# drone_controller.net
KiCad netlist of a schematic drawn in EAGLE
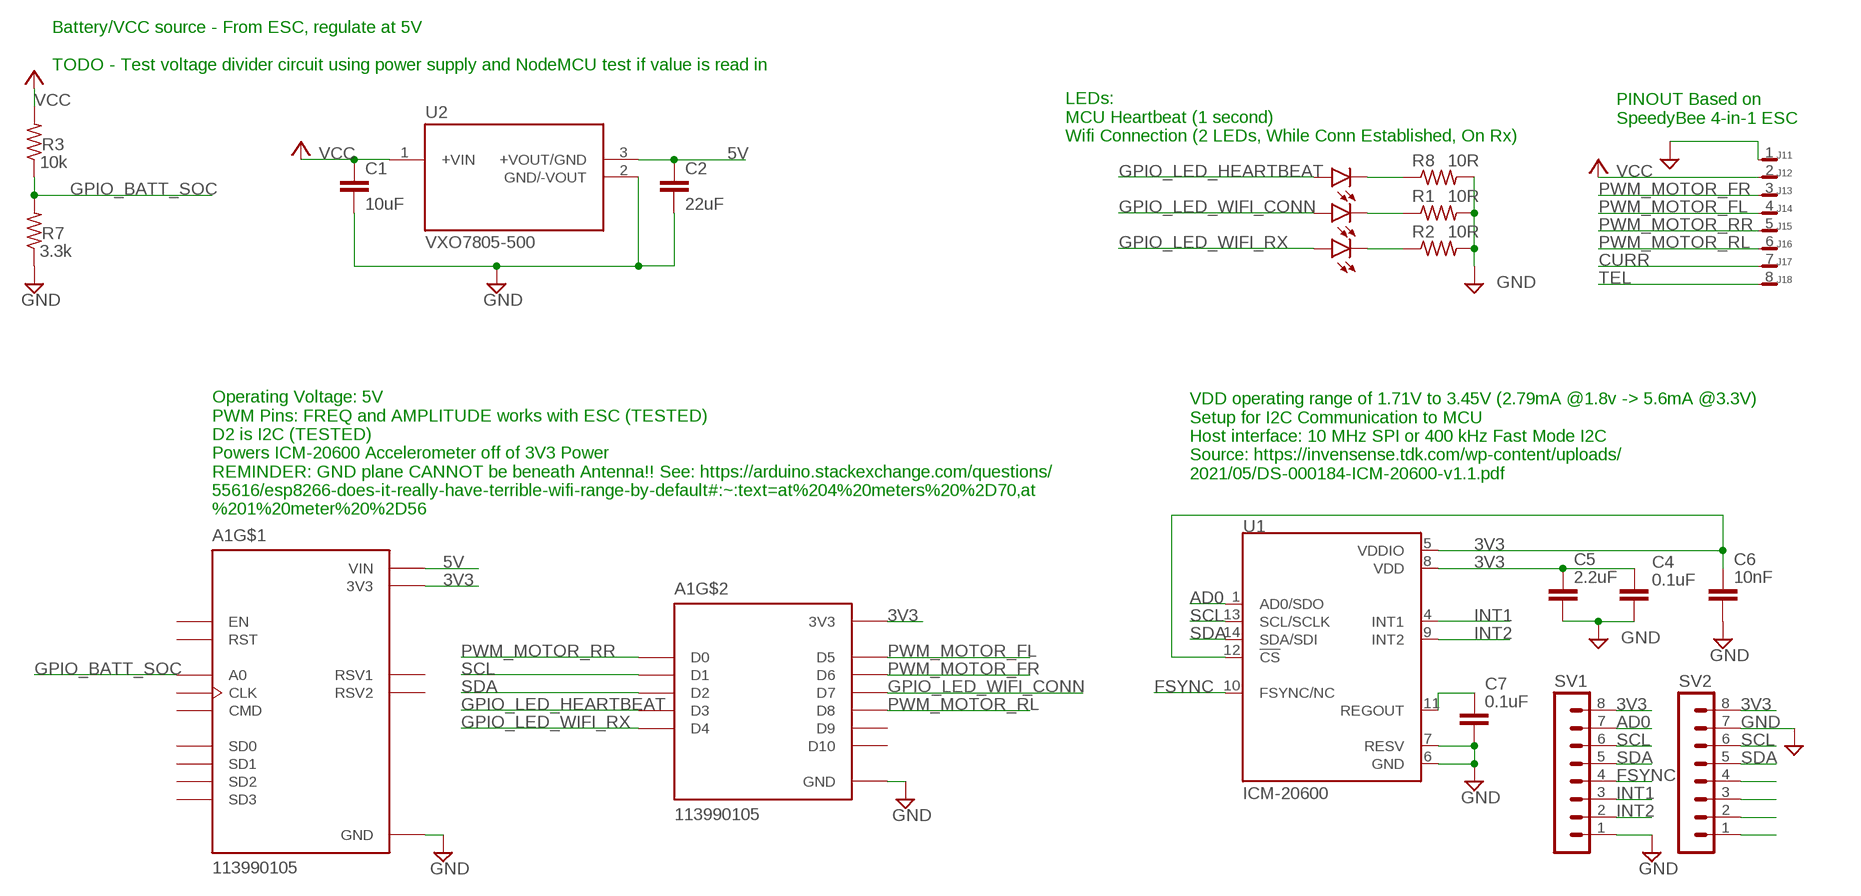
[diagram p0: schematic, sheet 1]

(export (version "E")
  (design (tool "Eeschema 10.0.6"))
  (components
    (comp (ref "A1")
      (value "113990105")
      (footprint "eagle-import:SEEED_113990105")
      (fields (field (name "MF") "Seeed Technology") (field (name "MP") "NodeMCU v2"))
      (libsource (lib "eagle-import") (part "113990105"))
    )
    (comp (ref "C1")
      (value "10uF")
      (footprint "eagle-import:C2.5-3")
      (libsource (lib "eagle-import") (part "C2,5-3"))
    )
    (comp (ref "C2")
      (value "22uF")
      (footprint "eagle-import:C2.5-3")
      (libsource (lib "eagle-import") (part "C2,5-3"))
    )
    (comp (ref "C4")
      (value "0.1uF")
      (footprint "eagle-import:C2.5-3")
      (libsource (lib "eagle-import") (part "C2,5-3"))
    )
    (comp (ref "C5")
      (value "2.2uF")
      (footprint "eagle-import:C2.5-3")
      (libsource (lib "eagle-import") (part "C2,5-3"))
    )
    (comp (ref "C6")
      (value "10nF")
      (footprint "eagle-import:C2.5-3")
      (libsource (lib "eagle-import") (part "C2,5-3"))
    )
    (comp (ref "C7")
      (value "0.1uF")
      (footprint "eagle-import:C2.5-3")
      (libsource (lib "eagle-import") (part "C2,5-3"))
    )
    (comp (ref "J1")
      (value "SM08B-SRSS-TB")
      (footprint "eagle-import:SM08B-SRSS-TB")
      (libsource (lib "eagle-import") (part "SM08B-SRSS-TB"))
    )
    (comp (ref "LED4")
      (value "LED5MM")
      (footprint "eagle-import:LED5MM")
      (libsource (lib "eagle-import") (part "LED5MM"))
    )
    (comp (ref "LED5")
      (value "LED5MM")
      (footprint "eagle-import:LED5MM")
      (libsource (lib "eagle-import") (part "LED5MM"))
    )
    (comp (ref "LED6")
      (value "LED5MM")
      (footprint "eagle-import:LED5MM")
      (libsource (lib "eagle-import") (part "LED5MM"))
    )
    (comp (ref "R1")
      (value "10R")
      (footprint "eagle-import:0204_7")
      (libsource (lib "eagle-import") (part "R-US_0204/7"))
    )
    (comp (ref "R2")
      (value "10R")
      (footprint "eagle-import:0204_7")
      (libsource (lib "eagle-import") (part "R-US_0204/7"))
    )
    (comp (ref "R3")
      (value "10k")
      (footprint "eagle-import:0204_7")
      (libsource (lib "eagle-import") (part "R-US_0204/7"))
    )
    (comp (ref "R7")
      (value "3.3k")
      (footprint "eagle-import:0204_7")
      (libsource (lib "eagle-import") (part "R-US_0204/7"))
    )
    (comp (ref "R8")
      (value "10R")
      (footprint "eagle-import:0204_7")
      (libsource (lib "eagle-import") (part "R-US_0204/7"))
    )
    (comp (ref "SV1")
      (value "MA08-1")
      (footprint "eagle-import:MA08-1")
      (libsource (lib "eagle-import") (part "MA08-1"))
    )
    (comp (ref "SV2")
      (value "MA08-1")
      (footprint "eagle-import:MA08-1")
      (libsource (lib "eagle-import") (part "MA08-1"))
    )
    (comp (ref "U1")
      (value "ICM-20600")
      (footprint "eagle-import:PQFN50P250X300X97-14N")
      (fields (field (name "MF") "TDK InvenSense"))
      (libsource (lib "eagle-import") (part "ICM-20600"))
    )
    (comp (ref "U2")
      (value "VXO7805-500")
      (footprint "eagle-import:CONV_VXO7805-500")
      (fields (field (name "MF") "CUI"))
      (libsource (lib "eagle-import") (part "VXO7805-500"))
    )
  )
  (nets
    (net (code "1") (name "/3V3") (class "Default")
      (node (ref "A1") (pin "J1_11") (pinfunction "3V3_J1_11") (pintype "power_in"))
      (node (ref "A1") (pin "J2_15") (pinfunction "3V3_J2_15") (pintype "power_in"))
      (node (ref "A1") (pin "J2_6") (pinfunction "3V3_J2_6") (pintype "power_in"))
      (node (ref "C4") (pin "1") (pinfunction "1_1") (pintype "passive"))
      (node (ref "C5") (pin "1") (pinfunction "1_1") (pintype "passive"))
      (node (ref "C6") (pin "1") (pinfunction "1_1") (pintype "passive"))
      (node (ref "SV1") (pin "8") (pinfunction "8_8") (pintype "passive"))
      (node (ref "SV2") (pin "8") (pinfunction "8_8") (pintype "passive"))
      (node (ref "U1") (pin "12") (pinfunction "~{CS}_12") (pintype "input"))
      (node (ref "U1") (pin "5") (pinfunction "VDDIO_5") (pintype "power_in"))
      (node (ref "U1") (pin "8") (pinfunction "VDD_8") (pintype "power_in"))
    )
    (net (code "2") (name "/5V") (class "Default")
      (node (ref "A1") (pin "J1_15") (pinfunction "VIN_J1_15") (pintype "power_in"))
      (node (ref "C2") (pin "1") (pinfunction "1_1") (pintype "passive"))
      (node (ref "U2") (pin "3") (pinfunction "+VOUT/GND_3") (pintype "output"))
    )
    (net (code "3") (name "/AD0") (class "Default")
      (node (ref "SV1") (pin "7") (pinfunction "7_7") (pintype "passive"))
      (node (ref "U1") (pin "1") (pinfunction "AD0/SDO_1") (pintype "output"))
    )
    (net (code "4") (name "/CURR") (class "Default")
      (node (ref "J1") (pin "7") (pinfunction "P_7") (pintype "bidirectional"))
    )
    (net (code "5") (name "/FSYNC") (class "Default")
      (node (ref "SV1") (pin "4") (pinfunction "4_4") (pintype "passive"))
      (node (ref "U1") (pin "10") (pinfunction "FSYNC/NC_10") (pintype "input"))
    )
    (net (code "6") (name "/GPIO_BATT_SOC") (class "Default")
      (node (ref "A1") (pin "J1_1") (pinfunction "A0_J1_1") (pintype "bidirectional"))
      (node (ref "R3") (pin "1") (pinfunction "1_1") (pintype "passive"))
      (node (ref "R7") (pin "2") (pinfunction "2_2") (pintype "passive"))
    )
    (net (code "7") (name "/GPIO_LED_HEARTBEAT") (class "Default")
      (node (ref "A1") (pin "J2_4") (pinfunction "D3_J2_4") (pintype "bidirectional"))
      (node (ref "LED4") (pin "A") (pinfunction "A_A") (pintype "passive"))
    )
    (net (code "8") (name "/GPIO_LED_WIFI_CONN") (class "Default")
      (node (ref "A1") (pin "J2_10") (pinfunction "D7_J2_10") (pintype "bidirectional"))
      (node (ref "LED5") (pin "A") (pinfunction "A_A") (pintype "passive"))
    )
    (net (code "9") (name "/GPIO_LED_WIFI_RX") (class "Default")
      (node (ref "A1") (pin "J2_5") (pinfunction "D4_J2_5") (pintype "bidirectional"))
      (node (ref "LED6") (pin "A") (pinfunction "A_A") (pintype "passive"))
    )
    (net (code "10") (name "/INT1") (class "Default")
      (node (ref "SV1") (pin "3") (pinfunction "3_3") (pintype "passive"))
      (node (ref "U1") (pin "4") (pinfunction "INT1_4") (pintype "output"))
    )
    (net (code "11") (name "/INT2") (class "Default")
      (node (ref "SV1") (pin "2") (pinfunction "2_2") (pintype "passive"))
      (node (ref "U1") (pin "9") (pinfunction "INT2_9") (pintype "output"))
    )
    (net (code "12") (name "/PWM_MOTOR_FL") (class "Default")
      (node (ref "A1") (pin "J2_8") (pinfunction "D5_J2_8") (pintype "bidirectional"))
      (node (ref "J1") (pin "4") (pinfunction "P_4") (pintype "bidirectional"))
    )
    (net (code "13") (name "/PWM_MOTOR_FR") (class "Default")
      (node (ref "A1") (pin "J2_9") (pinfunction "D6_J2_9") (pintype "bidirectional"))
      (node (ref "J1") (pin "3") (pinfunction "P_3") (pintype "bidirectional"))
    )
    (net (code "14") (name "/PWM_MOTOR_RL") (class "Default")
      (node (ref "A1") (pin "J2_11") (pinfunction "D8_J2_11") (pintype "bidirectional"))
      (node (ref "J1") (pin "6") (pinfunction "P_6") (pintype "bidirectional"))
    )
    (net (code "15") (name "/PWM_MOTOR_RR") (class "Default")
      (node (ref "A1") (pin "J2_1") (pinfunction "D0_J2_1") (pintype "bidirectional"))
      (node (ref "J1") (pin "5") (pinfunction "P_5") (pintype "bidirectional"))
    )
    (net (code "16") (name "/SCL") (class "Default")
      (node (ref "A1") (pin "J2_2") (pinfunction "D1_J2_2") (pintype "bidirectional"))
      (node (ref "SV1") (pin "6") (pinfunction "6_6") (pintype "passive"))
      (node (ref "SV2") (pin "6") (pinfunction "6_6") (pintype "passive"))
      (node (ref "U1") (pin "13") (pinfunction "SCL/SCLK_13") (pintype "bidirectional"))
    )
    (net (code "17") (name "/SDA") (class "Default")
      (node (ref "A1") (pin "J2_3") (pinfunction "D2_J2_3") (pintype "bidirectional"))
      (node (ref "SV1") (pin "5") (pinfunction "5_5") (pintype "passive"))
      (node (ref "SV2") (pin "5") (pinfunction "5_5") (pintype "passive"))
      (node (ref "U1") (pin "14") (pinfunction "SDA/SDI_14") (pintype "bidirectional"))
    )
    (net (code "18") (name "/TEL") (class "Default")
      (node (ref "J1") (pin "8") (pinfunction "P_8") (pintype "bidirectional"))
    )
    (net (code "19") (name "GND") (class "Default")
      (node (ref "A1") (pin "J1_10") (pinfunction "GND_J1_10") (pintype "power_in"))
      (node (ref "A1") (pin "J1_14") (pinfunction "GND_J1_14") (pintype "power_in"))
      (node (ref "A1") (pin "J2_14") (pinfunction "GND_J2_14") (pintype "power_in"))
      (node (ref "A1") (pin "J2_7") (pinfunction "GND_J2_7") (pintype "power_in"))
      (node (ref "C1") (pin "2") (pinfunction "2_2") (pintype "passive"))
      (node (ref "C2") (pin "2") (pinfunction "2_2") (pintype "passive"))
      (node (ref "C4") (pin "2") (pinfunction "2_2") (pintype "passive"))
      (node (ref "C5") (pin "2") (pinfunction "2_2") (pintype "passive"))
      (node (ref "C6") (pin "2") (pinfunction "2_2") (pintype "passive"))
      (node (ref "C7") (pin "2") (pinfunction "2_2") (pintype "passive"))
      (node (ref "J1") (pin "1") (pinfunction "P_1") (pintype "bidirectional"))
      (node (ref "R1") (pin "2") (pinfunction "2_2") (pintype "passive"))
      (node (ref "R2") (pin "2") (pinfunction "2_2") (pintype "passive"))
      (node (ref "R7") (pin "1") (pinfunction "1_1") (pintype "passive"))
      (node (ref "R8") (pin "2") (pinfunction "2_2") (pintype "passive"))
      (node (ref "SV1") (pin "1") (pinfunction "1_1") (pintype "passive"))
      (node (ref "SV2") (pin "7") (pinfunction "7_7") (pintype "passive"))
      (node (ref "U1") (pin "6") (pinfunction "GND_6") (pintype "power_in"))
      (node (ref "U1") (pin "7") (pinfunction "RESV_7") (pintype "power_in"))
      (node (ref "U2") (pin "2") (pinfunction "GND/-VOUT_2") (pintype "output"))
    )
    (net (code "20") (name "Net-(LED4-C)") (class "Default")
      (node (ref "LED4") (pin "K") (pinfunction "C_K") (pintype "passive"))
      (node (ref "R8") (pin "1") (pinfunction "1_1") (pintype "passive"))
    )
    (net (code "21") (name "Net-(LED5-C)") (class "Default")
      (node (ref "LED5") (pin "K") (pinfunction "C_K") (pintype "passive"))
      (node (ref "R1") (pin "1") (pinfunction "1_1") (pintype "passive"))
    )
    (net (code "22") (name "Net-(LED6-C)") (class "Default")
      (node (ref "LED6") (pin "K") (pinfunction "C_K") (pintype "passive"))
      (node (ref "R2") (pin "1") (pinfunction "1_1") (pintype "passive"))
    )
    (net (code "23") (name "Net-(U1-REGOUT)") (class "Default")
      (node (ref "C7") (pin "1") (pinfunction "1_1") (pintype "passive"))
      (node (ref "U1") (pin "11") (pinfunction "REGOUT_11") (pintype "passive"))
    )
    (net (code "24") (name "VCC") (class "Default")
      (node (ref "C1") (pin "1") (pinfunction "1_1") (pintype "passive"))
      (node (ref "J1") (pin "2") (pinfunction "P_2") (pintype "bidirectional"))
      (node (ref "R3") (pin "2") (pinfunction "2_2") (pintype "passive"))
      (node (ref "U2") (pin "1") (pinfunction "+VIN_1") (pintype "input"))
    )
    (net (code "25") (name "unconnected-(A1A-CLK-PadJ1_9)") (class "Default")
      (node (ref "A1") (pin "J1_9") (pinfunction "CLK_J1_9") (pintype "bidirectional"))
    )
    (net (code "26") (name "unconnected-(A1A-CMD-PadJ1_7)") (class "Default")
      (node (ref "A1") (pin "J1_7") (pinfunction "CMD_J1_7") (pintype "bidirectional"))
    )
    (net (code "27") (name "unconnected-(A1A-EN-PadJ1_12)") (class "Default")
      (node (ref "A1") (pin "J1_12") (pinfunction "EN_J1_12") (pintype "input"))
    )
    (net (code "28") (name "unconnected-(A1A-RST-PadJ1_13)") (class "Default")
      (node (ref "A1") (pin "J1_13") (pinfunction "RST_J1_13") (pintype "input"))
    )
    (net (code "29") (name "unconnected-(A1A-RSV1-PadJ1_2)") (class "Default")
      (node (ref "A1") (pin "J1_2") (pinfunction "RSV1_J1_2") (pintype "bidirectional"))
    )
    (net (code "30") (name "unconnected-(A1A-RSV2-PadJ1_3)") (class "Default")
      (node (ref "A1") (pin "J1_3") (pinfunction "RSV2_J1_3") (pintype "bidirectional"))
    )
    (net (code "31") (name "unconnected-(A1A-SD0-PadJ1_8)") (class "Default")
      (node (ref "A1") (pin "J1_8") (pinfunction "SD0_J1_8") (pintype "bidirectional"))
    )
    (net (code "32") (name "unconnected-(A1A-SD1-PadJ1_6)") (class "Default")
      (node (ref "A1") (pin "J1_6") (pinfunction "SD1_J1_6") (pintype "bidirectional"))
    )
    (net (code "33") (name "unconnected-(A1A-SD2-PadJ1_5)") (class "Default")
      (node (ref "A1") (pin "J1_5") (pinfunction "SD2_J1_5") (pintype "bidirectional"))
    )
    (net (code "34") (name "unconnected-(A1A-SD3-PadJ1_4)") (class "Default")
      (node (ref "A1") (pin "J1_4") (pinfunction "SD3_J1_4") (pintype "bidirectional"))
    )
    (net (code "35") (name "unconnected-(A1B-D9-PadJ2_12)") (class "Default")
      (node (ref "A1") (pin "J2_12") (pinfunction "D9_J2_12") (pintype "bidirectional"))
    )
    (net (code "36") (name "unconnected-(A1B-D10-PadJ2_13)") (class "Default")
      (node (ref "A1") (pin "J2_13") (pinfunction "D10_J2_13") (pintype "bidirectional"))
    )
    (net (code "37") (name "unconnected-(SV2-Pad1)") (class "Default")
      (node (ref "SV2") (pin "1") (pinfunction "1_1") (pintype "passive"))
    )
    (net (code "38") (name "unconnected-(SV2-Pad2)") (class "Default")
      (node (ref "SV2") (pin "2") (pinfunction "2_2") (pintype "passive"))
    )
    (net (code "39") (name "unconnected-(SV2-Pad3)") (class "Default")
      (node (ref "SV2") (pin "3") (pinfunction "3_3") (pintype "passive"))
    )
    (net (code "40") (name "unconnected-(SV2-Pad4)") (class "Default")
      (node (ref "SV2") (pin "4") (pinfunction "4_4") (pintype "passive"))
    )
  )
)
